# projeto_sistemas_embarcados_2.net
KiCad netlist of a schematic drawn in EAGLE
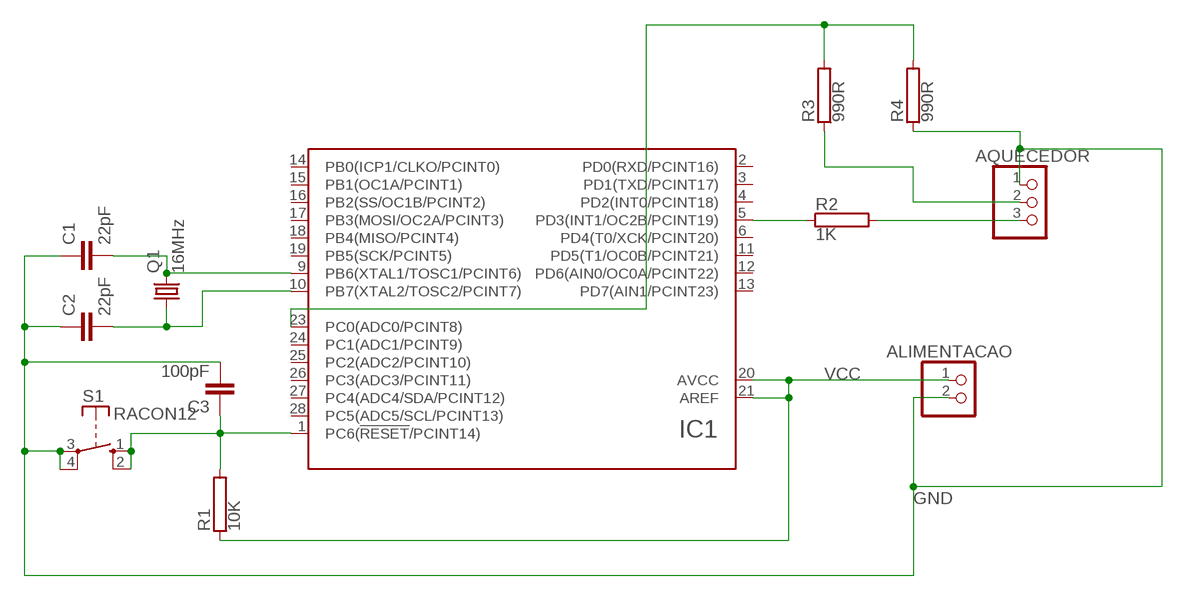
[diagram p0: schematic, sheet 1]

(export (version "E")
  (design (tool "Eeschema 10.0.6"))
  (components
    (comp (ref "ALIMENTACAO")
      (value "PINHD-1X2")
      (footprint "eagle-import:1X02")
      (libsource (lib "eagle-import") (part "PINHD-1X2"))
    )
    (comp (ref "AQUECEDOR")
      (value "PINHD-1X3")
      (footprint "eagle-import:1X03")
      (libsource (lib "eagle-import") (part "PINHD-1X3"))
    )
    (comp (ref "C1")
      (value "22pF")
      (footprint "eagle-import:C2.5-3")
      (libsource (lib "eagle-import") (part "C2,5-3"))
    )
    (comp (ref "C2")
      (value "22pF")
      (footprint "eagle-import:C2.5-3")
      (libsource (lib "eagle-import") (part "C2,5-3"))
    )
    (comp (ref "C3")
      (value "100pF")
      (footprint "eagle-import:C2.5-3")
      (libsource (lib "eagle-import") (part "C2,5-3"))
    )
    (comp (ref "IC1")
      (value "ATMEGA48/88/168/328-PU(DIP28)PU")
      (footprint "eagle-import:DIL28")
      (libsource (lib "eagle-import") (part "ATMEGA48/88/168/328-PU(DIP28)PU"))
    )
    (comp (ref "Q1")
      (value "16MHz")
      (footprint "eagle-import:HC49_S")
      (libsource (lib "eagle-import") (part "CRYSTALHC49S"))
    )
    (comp (ref "R1")
      (value "10K")
      (footprint "eagle-import:AC01")
      (libsource (lib "eagle-import") (part "RAC01"))
    )
    (comp (ref "R2")
      (value "1K")
      (footprint "eagle-import:AC01")
      (libsource (lib "eagle-import") (part "RAC01"))
    )
    (comp (ref "R3")
      (value "990R")
      (footprint "eagle-import:HPS63")
      (libsource (lib "eagle-import") (part "RHPS63"))
    )
    (comp (ref "R4")
      (value "990R")
      (footprint "eagle-import:AC01")
      (libsource (lib "eagle-import") (part "RAC01"))
    )
    (comp (ref "S1")
      (value "RACON12")
      (footprint "eagle-import:RACON12")
      (libsource (lib "eagle-import") (part "RACON12"))
    )
  )
  (nets
    (net (code "1") (name "/GND") (class "Default")
      (node (ref "ALIMENTACAO") (pin "2") (pinfunction "2_2") (pintype "passive"))
      (node (ref "AQUECEDOR") (pin "1") (pinfunction "1_1") (pintype "passive"))
      (node (ref "C1") (pin "1") (pinfunction "1_1") (pintype "passive"))
      (node (ref "C2") (pin "1") (pinfunction "1_1") (pintype "passive"))
      (node (ref "C3") (pin "2") (pinfunction "2_2") (pintype "passive"))
      (node (ref "R4") (pin "1") (pinfunction "1_1") (pintype "passive"))
      (node (ref "S1") (pin "3") (pinfunction "P_3") (pintype "passive"))
      (node (ref "S1") (pin "4") (pinfunction "P_4") (pintype "passive"))
    )
    (net (code "2") (name "/VCC") (class "Default")
      (node (ref "ALIMENTACAO") (pin "1") (pinfunction "1_1") (pintype "passive"))
      (node (ref "IC1") (pin "20") (pinfunction "AVCC_20") (pintype "power_in"))
      (node (ref "IC1") (pin "21") (pinfunction "AREF_21") (pintype "passive"))
      (node (ref "R1") (pin "1") (pinfunction "1_1") (pintype "passive"))
    )
    (net (code "3") (name "Net-(AQUECEDOR-Pad2)") (class "Default")
      (node (ref "AQUECEDOR") (pin "2") (pinfunction "2_2") (pintype "passive"))
      (node (ref "R3") (pin "1") (pinfunction "1_1") (pintype "passive"))
    )
    (net (code "4") (name "Net-(AQUECEDOR-Pad3)") (class "Default")
      (node (ref "AQUECEDOR") (pin "3") (pinfunction "3_3") (pintype "passive"))
      (node (ref "R2") (pin "2") (pinfunction "2_2") (pintype "passive"))
    )
    (net (code "5") (name "Net-(IC1A-PB6(XTAL1{slash}TOSC1{slash}PCINT6))") (class "Default")
      (node (ref "C1") (pin "2") (pinfunction "2_2") (pintype "passive"))
      (node (ref "IC1") (pin "9") (pinfunction "PB6(XTAL1/TOSC1/PCINT6)_9") (pintype "bidirectional"))
      (node (ref "Q1") (pin "2") (pinfunction "2_2") (pintype "passive"))
    )
    (net (code "6") (name "Net-(IC1A-PB7(XTAL2{slash}TOSC2{slash}PCINT7))") (class "Default")
      (node (ref "C2") (pin "2") (pinfunction "2_2") (pintype "passive"))
      (node (ref "IC1") (pin "10") (pinfunction "PB7(XTAL2/TOSC2/PCINT7)_10") (pintype "bidirectional"))
      (node (ref "Q1") (pin "1") (pinfunction "1_1") (pintype "passive"))
    )
    (net (code "7") (name "Net-(IC1A-PC0(ADC0{slash}PCINT8))") (class "Default")
      (node (ref "IC1") (pin "23") (pinfunction "PC0(ADC0/PCINT8)_23") (pintype "bidirectional"))
      (node (ref "R3") (pin "2") (pinfunction "2_2") (pintype "passive"))
      (node (ref "R4") (pin "2") (pinfunction "2_2") (pintype "passive"))
    )
    (net (code "8") (name "Net-(IC1A-PC6(~{RESET}{slash}PCINT14))") (class "Default")
      (node (ref "C3") (pin "1") (pinfunction "1_1") (pintype "passive"))
      (node (ref "IC1") (pin "1") (pinfunction "PC6(~{RESET}/PCINT14)_1") (pintype "bidirectional"))
      (node (ref "R1") (pin "2") (pinfunction "2_2") (pintype "passive"))
      (node (ref "S1") (pin "1") (pinfunction "S_1") (pintype "passive"))
      (node (ref "S1") (pin "2") (pinfunction "S_2") (pintype "passive"))
    )
    (net (code "9") (name "Net-(IC1A-PD3(INT1{slash}OC2B{slash}PCINT19))") (class "Default")
      (node (ref "IC1") (pin "5") (pinfunction "PD3(INT1/OC2B/PCINT19)_5") (pintype "bidirectional"))
      (node (ref "R2") (pin "1") (pinfunction "1_1") (pintype "passive"))
    )
    (net (code "10") (name "unconnected-(IC1A-PB0(ICP1{slash}CLKO{slash}PCINT0)-Pad14)") (class "Default")
      (node (ref "IC1") (pin "14") (pinfunction "PB0(ICP1/CLKO/PCINT0)_14") (pintype "bidirectional"))
    )
    (net (code "11") (name "unconnected-(IC1A-PB1(OC1A{slash}PCINT1)-Pad15)") (class "Default")
      (node (ref "IC1") (pin "15") (pinfunction "PB1(OC1A/PCINT1)_15") (pintype "bidirectional"))
    )
    (net (code "12") (name "unconnected-(IC1A-PB2(SS{slash}OC1B{slash}PCINT2)-Pad16)") (class "Default")
      (node (ref "IC1") (pin "16") (pinfunction "PB2(SS/OC1B/PCINT2)_16") (pintype "bidirectional"))
    )
    (net (code "13") (name "unconnected-(IC1A-PB3(MOSI{slash}OC2A{slash}PCINT3)-Pad17)") (class "Default")
      (node (ref "IC1") (pin "17") (pinfunction "PB3(MOSI/OC2A/PCINT3)_17") (pintype "bidirectional"))
    )
    (net (code "14") (name "unconnected-(IC1A-PB4(MISO{slash}PCINT4)-Pad18)") (class "Default")
      (node (ref "IC1") (pin "18") (pinfunction "PB4(MISO/PCINT4)_18") (pintype "bidirectional"))
    )
    (net (code "15") (name "unconnected-(IC1A-PB5(SCK{slash}PCINT5)-Pad19)") (class "Default")
      (node (ref "IC1") (pin "19") (pinfunction "PB5(SCK/PCINT5)_19") (pintype "bidirectional"))
    )
    (net (code "16") (name "unconnected-(IC1A-PC1(ADC1{slash}PCINT9)-Pad24)") (class "Default")
      (node (ref "IC1") (pin "24") (pinfunction "PC1(ADC1/PCINT9)_24") (pintype "bidirectional"))
    )
    (net (code "17") (name "unconnected-(IC1A-PC2(ADC2{slash}PCINT10)-Pad25)") (class "Default")
      (node (ref "IC1") (pin "25") (pinfunction "PC2(ADC2/PCINT10)_25") (pintype "bidirectional"))
    )
    (net (code "18") (name "unconnected-(IC1A-PC3(ADC3{slash}PCINT11)-Pad26)") (class "Default")
      (node (ref "IC1") (pin "26") (pinfunction "PC3(ADC3/PCINT11)_26") (pintype "bidirectional"))
    )
    (net (code "19") (name "unconnected-(IC1A-PC4(ADC4{slash}SDA{slash}PCINT12)-Pad27)") (class "Default")
      (node (ref "IC1") (pin "27") (pinfunction "PC4(ADC4/SDA/PCINT12)_27") (pintype "bidirectional"))
    )
    (net (code "20") (name "unconnected-(IC1A-PC5(ADC5{slash}SCL{slash}PCINT13)-Pad28)") (class "Default")
      (node (ref "IC1") (pin "28") (pinfunction "PC5(ADC5/SCL/PCINT13)_28") (pintype "bidirectional"))
    )
    (net (code "21") (name "unconnected-(IC1A-PD0(RXD{slash}PCINT16)-Pad2)") (class "Default")
      (node (ref "IC1") (pin "2") (pinfunction "PD0(RXD/PCINT16)_2") (pintype "bidirectional"))
    )
    (net (code "22") (name "unconnected-(IC1A-PD1(TXD{slash}PCINT17)-Pad3)") (class "Default")
      (node (ref "IC1") (pin "3") (pinfunction "PD1(TXD/PCINT17)_3") (pintype "bidirectional"))
    )
    (net (code "23") (name "unconnected-(IC1A-PD2(INT0{slash}PCINT18)-Pad4)") (class "Default")
      (node (ref "IC1") (pin "4") (pinfunction "PD2(INT0/PCINT18)_4") (pintype "bidirectional"))
    )
    (net (code "24") (name "unconnected-(IC1A-PD4(T0{slash}XCK{slash}PCINT20)-Pad6)") (class "Default")
      (node (ref "IC1") (pin "6") (pinfunction "PD4(T0/XCK/PCINT20)_6") (pintype "bidirectional"))
    )
    (net (code "25") (name "unconnected-(IC1A-PD5(T1{slash}OC0B{slash}PCINT21)-Pad11)") (class "Default")
      (node (ref "IC1") (pin "11") (pinfunction "PD5(T1/OC0B/PCINT21)_11") (pintype "bidirectional"))
    )
    (net (code "26") (name "unconnected-(IC1A-PD6(AIN0{slash}OC0A{slash}PCINT22)-Pad12)") (class "Default")
      (node (ref "IC1") (pin "12") (pinfunction "PD6(AIN0/OC0A/PCINT22)_12") (pintype "bidirectional"))
    )
    (net (code "27") (name "unconnected-(IC1A-PD7(AIN1{slash}PCINT23)-Pad13)") (class "Default")
      (node (ref "IC1") (pin "13") (pinfunction "PD7(AIN1/PCINT23)_13") (pintype "bidirectional"))
    )
  )
)
